# RoboSkinRev2.net
KiCad netlist of a schematic drawn in EAGLE
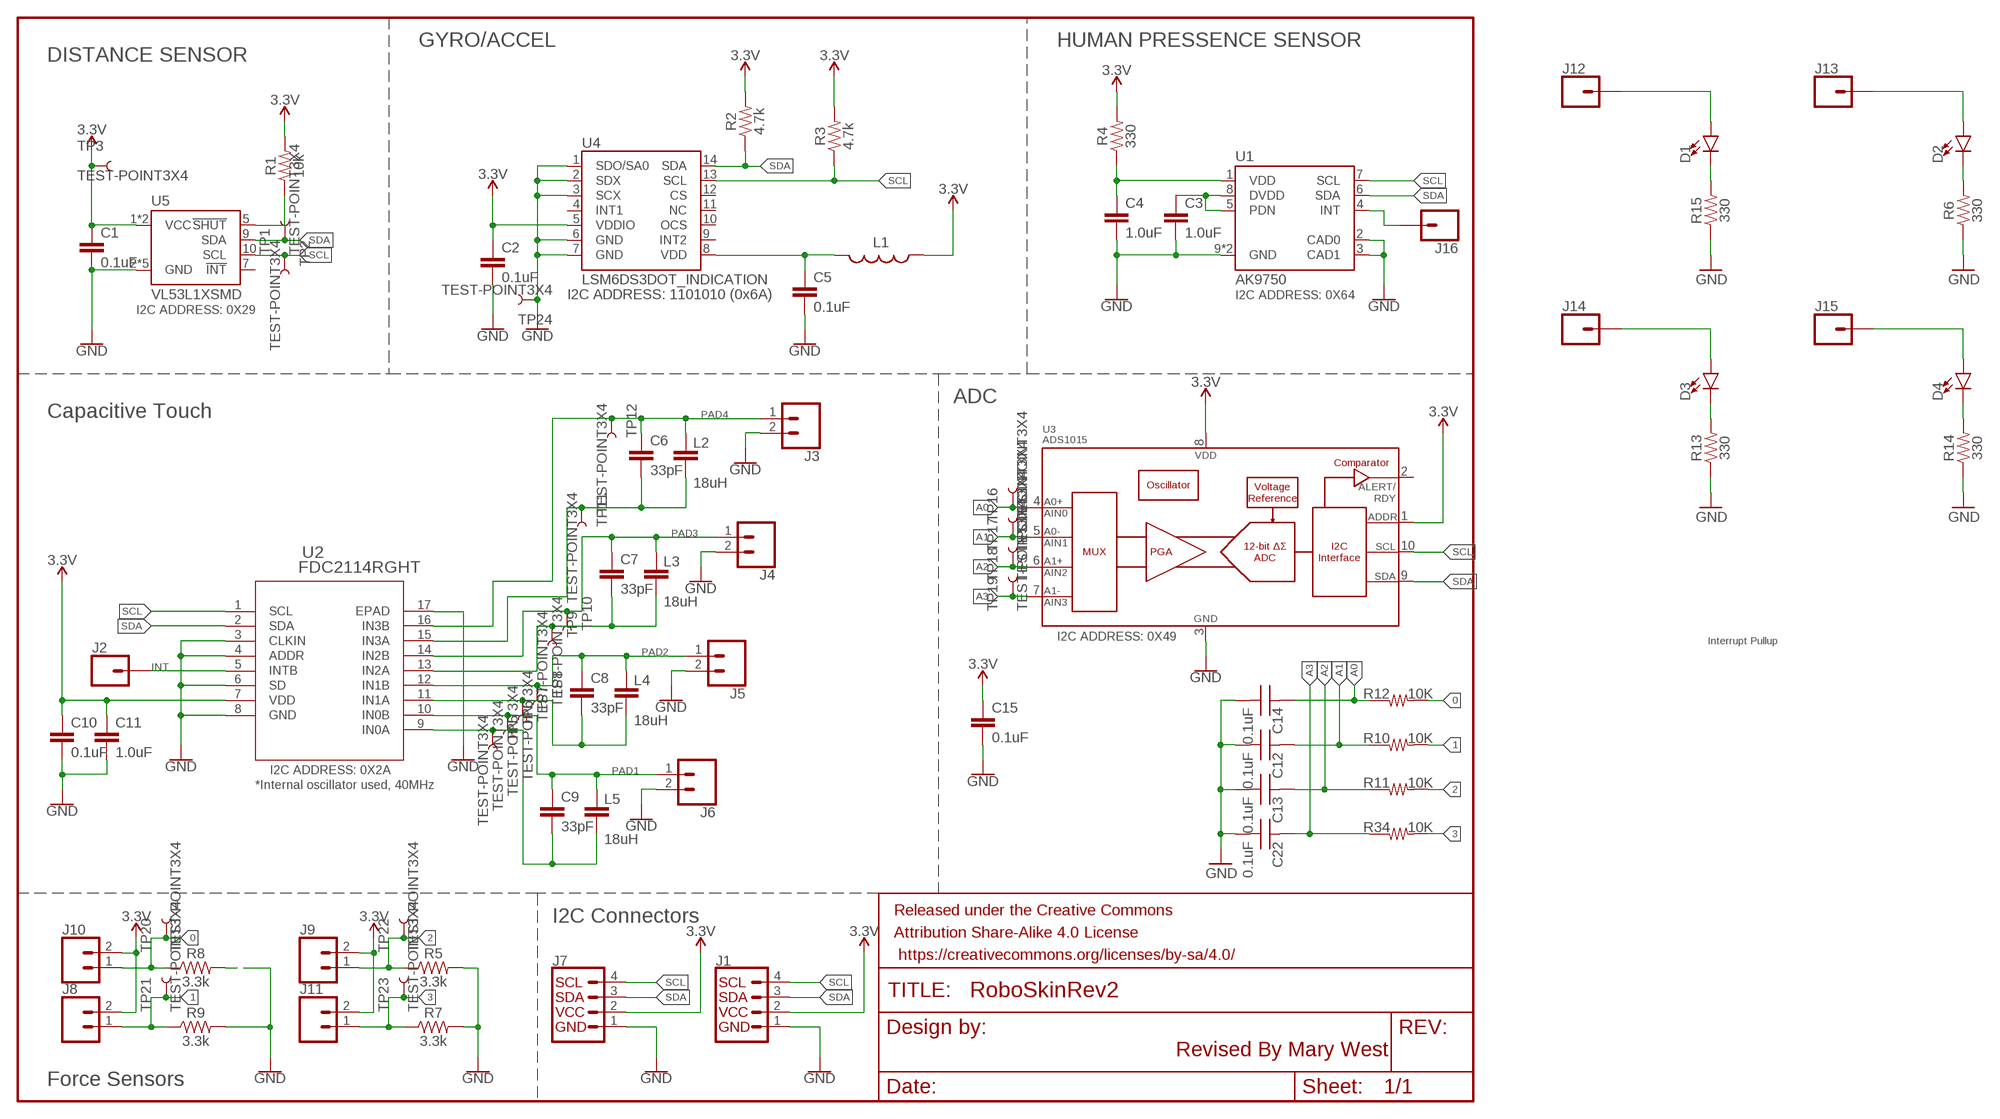
[diagram p0: schematic, sheet 1]

(export (version "E")
  (design (tool "Eeschema 10.0.6"))
  (components
    (comp (ref "C1")
      (value "0.1uF")
      (footprint "eagle-import:0603")
      (libsource (lib "eagle-import") (part "0.1UF-0603-25V-(+80/-20%)"))
    )
    (comp (ref "C2")
      (value "0.1uF")
      (footprint "eagle-import:0603")
      (libsource (lib "eagle-import") (part "0.1UF-0603-25V-(+80/-20%)"))
    )
    (comp (ref "C3")
      (value "1.0uF")
      (footprint "eagle-import:0603")
      (libsource (lib "eagle-import") (part "1.0UF-0603-16V-10%"))
    )
    (comp (ref "C4")
      (value "1.0uF")
      (footprint "eagle-import:0603")
      (libsource (lib "eagle-import") (part "1.0UF-0603-16V-10%"))
    )
    (comp (ref "C5")
      (value "0.1uF")
      (footprint "eagle-import:0603")
      (libsource (lib "eagle-import") (part "0.1UF-0603-25V-(+80/-20%)"))
    )
    (comp (ref "C6")
      (value "33pF")
      (footprint "eagle-import:0603")
      (libsource (lib "eagle-import") (part "33PF-0603-50V-5%"))
    )
    (comp (ref "C7")
      (value "33pF")
      (footprint "eagle-import:0603")
      (libsource (lib "eagle-import") (part "33PF-0603-50V-5%"))
    )
    (comp (ref "C8")
      (value "33pF")
      (footprint "eagle-import:0603")
      (libsource (lib "eagle-import") (part "33PF-0603-50V-5%"))
    )
    (comp (ref "C9")
      (value "33pF")
      (footprint "eagle-import:0603")
      (libsource (lib "eagle-import") (part "33PF-0603-50V-5%"))
    )
    (comp (ref "C10")
      (value "0.1uF")
      (footprint "eagle-import:0603")
      (libsource (lib "eagle-import") (part "0.1UF-0603-25V-(+80/-20%)"))
    )
    (comp (ref "C11")
      (value "1.0uF")
      (footprint "eagle-import:0603")
      (libsource (lib "eagle-import") (part "1.0UF-0603-16V-10%"))
    )
    (comp (ref "C12")
      (value "0.1uF")
      (footprint "eagle-import:0603_SILK")
      (fields (field (name "PARTNO") "GRM188R70J104KA01D"))
      (libsource (lib "eagle-import") (part "CAPACITORC_0603_SILK"))
    )
    (comp (ref "C13")
      (value "0.1uF")
      (footprint "eagle-import:0603_SILK")
      (fields (field (name "PARTNO") "GRM188R70J104KA01D"))
      (libsource (lib "eagle-import") (part "CAPACITORC_0603_SILK"))
    )
    (comp (ref "C14")
      (value "0.1uF")
      (footprint "eagle-import:0603_SILK")
      (fields (field (name "PARTNO") "GRM188R70J104KA01D"))
      (libsource (lib "eagle-import") (part "CAPACITORC_0603_SILK"))
    )
    (comp (ref "C15")
      (value "0.1uF")
      (footprint "eagle-import:0603")
      (libsource (lib "eagle-import") (part "0.1UF-0603-25V-(+80/-20%)"))
    )
    (comp (ref "C22")
      (value "0.1uF")
      (footprint "eagle-import:0603_SILK")
      (fields (field (name "PARTNO") "GRM188R70J104KA01D"))
      (libsource (lib "eagle-import") (part "CAPACITORC_0603_SILK"))
    )
    (comp (ref "D1")
      (value "LED1206")
      (footprint "eagle-import:LED-1206")
      (libsource (lib "eagle-import") (part "LED1206"))
    )
    (comp (ref "D2")
      (value "LED1206")
      (footprint "eagle-import:LED-1206")
      (libsource (lib "eagle-import") (part "LED1206"))
    )
    (comp (ref "D3")
      (value "LED1206")
      (footprint "eagle-import:LED-1206")
      (libsource (lib "eagle-import") (part "LED1206"))
    )
    (comp (ref "D4")
      (value "LED1206")
      (footprint "eagle-import:LED-1206")
      (libsource (lib "eagle-import") (part "LED1206"))
    )
    (comp (ref "FRAME1")
      (value "FRAME-LETTERNO_PACKAGE")
      (footprint "eagle-import:DUMMY")
      (fields (field (name "DESIGNER") "Nobody"))
      (libsource (lib "eagle-import") (part "FRAME-LETTERNO_PACKAGE"))
    )
    (comp (ref "J1")
      (value "QWIIC_CONNECTORJS-1MM")
      (footprint "eagle-import:1X04_1MM_RA")
      (libsource (lib "eagle-import") (part "QWIIC_CONNECTORJS-1MM"))
    )
    (comp (ref "J2")
      (value "CONN_01")
      (footprint "eagle-import:1X01")
      (libsource (lib "eagle-import") (part "CONN_01"))
    )
    (comp (ref "J3")
      (value "CONN_02")
      (footprint "eagle-import:1X02")
      (libsource (lib "eagle-import") (part "CONN_02"))
    )
    (comp (ref "J4")
      (value "CONN_02")
      (footprint "eagle-import:1X02")
      (libsource (lib "eagle-import") (part "CONN_02"))
    )
    (comp (ref "J5")
      (value "CONN_02")
      (footprint "eagle-import:1X02")
      (libsource (lib "eagle-import") (part "CONN_02"))
    )
    (comp (ref "J6")
      (value "CONN_02")
      (footprint "eagle-import:1X02")
      (libsource (lib "eagle-import") (part "CONN_02"))
    )
    (comp (ref "J7")
      (value "QWIIC_CONNECTORJS-1MM")
      (footprint "eagle-import:1X04_1MM_RA")
      (libsource (lib "eagle-import") (part "QWIIC_CONNECTORJS-1MM"))
    )
    (comp (ref "J8")
      (value "CONN_02")
      (footprint "eagle-import:1X02")
      (libsource (lib "eagle-import") (part "CONN_02"))
    )
    (comp (ref "J9")
      (value "CONN_02")
      (footprint "eagle-import:1X02")
      (libsource (lib "eagle-import") (part "CONN_02"))
    )
    (comp (ref "J10")
      (value "CONN_02")
      (footprint "eagle-import:1X02")
      (libsource (lib "eagle-import") (part "CONN_02"))
    )
    (comp (ref "J11")
      (value "CONN_02")
      (footprint "eagle-import:1X02")
      (libsource (lib "eagle-import") (part "CONN_02"))
    )
    (comp (ref "J12")
      (value "CONN_01")
      (footprint "eagle-import:1X01")
      (libsource (lib "eagle-import") (part "CONN_01"))
    )
    (comp (ref "J13")
      (value "CONN_01")
      (footprint "eagle-import:1X01")
      (libsource (lib "eagle-import") (part "CONN_01"))
    )
    (comp (ref "J14")
      (value "CONN_01")
      (footprint "eagle-import:1X01")
      (libsource (lib "eagle-import") (part "CONN_01"))
    )
    (comp (ref "J15")
      (value "CONN_01")
      (footprint "eagle-import:1X01")
      (libsource (lib "eagle-import") (part "CONN_01"))
    )
    (comp (ref "J16")
      (value "CONN_01PTH_NO_SILK_YES_STOP")
      (footprint "eagle-import:1X01_NO_SILK")
      (libsource (lib "eagle-import") (part "CONN_01PTH_NO_SILK_YES_STOP"))
    )
    (comp (ref "L1")
      (value "RES-07859")
      (footprint "eagle-import:0603")
      (libsource (lib "eagle-import") (part "INDUCTOR30OHM,1.8A"))
    )
    (comp (ref "L2")
      (value "18uH")
      (footprint "eagle-import:1210")
      (libsource (lib "eagle-import") (part "100UF6.3V20%(1210)"))
    )
    (comp (ref "L3")
      (value "18uH")
      (footprint "eagle-import:1210")
      (libsource (lib "eagle-import") (part "100UF6.3V20%(1210)"))
    )
    (comp (ref "L4")
      (value "18uH")
      (footprint "eagle-import:1210")
      (libsource (lib "eagle-import") (part "100UF6.3V20%(1210)"))
    )
    (comp (ref "L5")
      (value "18uH")
      (footprint "eagle-import:1210")
      (libsource (lib "eagle-import") (part "100UF6.3V20%(1210)"))
    )
    (comp (ref "R1")
      (value "10k")
      (footprint "eagle-import:0603")
      (libsource (lib "eagle-import") (part "10KOHM-0603-1/10W-1%"))
    )
    (comp (ref "R2")
      (value "4.7k")
      (footprint "eagle-import:0603")
      (libsource (lib "eagle-import") (part "4.7KOHM-0603-1/10W-1%"))
    )
    (comp (ref "R3")
      (value "4.7k")
      (footprint "eagle-import:0603")
      (libsource (lib "eagle-import") (part "4.7KOHM-0603-1/10W-1%"))
    )
    (comp (ref "R4")
      (value "330")
      (footprint "eagle-import:0603")
      (libsource (lib "eagle-import") (part "SparkFun-Resistors_532_330OHM-0603-1/10W-1%"))
    )
    (comp (ref "R5")
      (value "3.3k")
      (footprint "eagle-import:0603")
      (libsource (lib "eagle-import") (part "3.3KOHM-0603-1/10W-1%"))
    )
    (comp (ref "R6")
      (value "330")
      (footprint "eagle-import:0603")
      (libsource (lib "eagle-import") (part "330OHM-0603-1/10W-1%"))
    )
    (comp (ref "R7")
      (value "3.3k")
      (footprint "eagle-import:0603")
      (libsource (lib "eagle-import") (part "3.3KOHM-0603-1/10W-1%"))
    )
    (comp (ref "R8")
      (value "3.3k")
      (footprint "eagle-import:0603")
      (libsource (lib "eagle-import") (part "3.3KOHM-0603-1/10W-1%"))
    )
    (comp (ref "R9")
      (value "3.3k")
      (footprint "eagle-import:0603")
      (libsource (lib "eagle-import") (part "3.3KOHM-0603-1/10W-1%"))
    )
    (comp (ref "R10")
      (value "10K")
      (footprint "eagle-import:0603_SILK")
      (fields (field (name "PARTNO") "CR0603-FX-1002ELF"))
      (libsource (lib "eagle-import") (part "RESISTORR_0603_SILK"))
    )
    (comp (ref "R11")
      (value "10K")
      (footprint "eagle-import:0603_SILK")
      (fields (field (name "PARTNO") "CR0603-FX-1002ELF"))
      (libsource (lib "eagle-import") (part "RESISTORR_0603_SILK"))
    )
    (comp (ref "R12")
      (value "10K")
      (footprint "eagle-import:0603_SILK")
      (fields (field (name "PARTNO") "CR0603-FX-1002ELF"))
      (libsource (lib "eagle-import") (part "RESISTORR_0603_SILK"))
    )
    (comp (ref "R13")
      (value "330")
      (footprint "eagle-import:0603")
      (libsource (lib "eagle-import") (part "330OHM-0603-1/10W-1%"))
    )
    (comp (ref "R14")
      (value "330")
      (footprint "eagle-import:0603")
      (libsource (lib "eagle-import") (part "330OHM-0603-1/10W-1%"))
    )
    (comp (ref "R15")
      (value "330")
      (footprint "eagle-import:0603")
      (libsource (lib "eagle-import") (part "330OHM-0603-1/10W-1%"))
    )
    (comp (ref "R34")
      (value "10K")
      (footprint "eagle-import:0603_SILK")
      (fields (field (name "PARTNO") "CR0603-FX-1002ELF"))
      (libsource (lib "eagle-import") (part "RESISTORR_0603_SILK"))
    )
    (comp (ref "TP1")
      (value "TEST-POINT3X4")
      (footprint "eagle-import:PAD.03X.04")
      (libsource (lib "eagle-import") (part "TEST-POINT3X4"))
    )
    (comp (ref "TP2")
      (value "TEST-POINT3X4")
      (footprint "eagle-import:PAD.03X.04")
      (libsource (lib "eagle-import") (part "TEST-POINT3X4"))
    )
    (comp (ref "TP3")
      (value "TEST-POINT3X4")
      (footprint "eagle-import:PAD.03X.04")
      (libsource (lib "eagle-import") (part "TEST-POINT3X4"))
    )
    (comp (ref "TP5")
      (value "TEST-POINT3X4")
      (footprint "eagle-import:PAD.03X.04")
      (libsource (lib "eagle-import") (part "TEST-POINT3X4"))
    )
    (comp (ref "TP6")
      (value "TEST-POINT3X4")
      (footprint "eagle-import:PAD.03X.04")
      (libsource (lib "eagle-import") (part "TEST-POINT3X4"))
    )
    (comp (ref "TP7")
      (value "TEST-POINT3X4")
      (footprint "eagle-import:PAD.03X.04")
      (libsource (lib "eagle-import") (part "TEST-POINT3X4"))
    )
    (comp (ref "TP8")
      (value "TEST-POINT3X4")
      (footprint "eagle-import:PAD.03X.04")
      (libsource (lib "eagle-import") (part "TEST-POINT3X4"))
    )
    (comp (ref "TP9")
      (value "TEST-POINT3X4")
      (footprint "eagle-import:PAD.03X.04")
      (libsource (lib "eagle-import") (part "TEST-POINT3X4"))
    )
    (comp (ref "TP10")
      (value "TEST-POINT3X4")
      (footprint "eagle-import:PAD.03X.04")
      (libsource (lib "eagle-import") (part "TEST-POINT3X4"))
    )
    (comp (ref "TP11")
      (value "TEST-POINT3X4")
      (footprint "eagle-import:PAD.03X.04")
      (libsource (lib "eagle-import") (part "TEST-POINT3X4"))
    )
    (comp (ref "TP12")
      (value "TEST-POINT3X4")
      (footprint "eagle-import:PAD.03X.04")
      (libsource (lib "eagle-import") (part "TEST-POINT3X4"))
    )
    (comp (ref "TP16")
      (value "TEST-POINT3X4")
      (footprint "eagle-import:PAD.03X.04")
      (libsource (lib "eagle-import") (part "TEST-POINT3X4"))
    )
    (comp (ref "TP17")
      (value "TEST-POINT3X4")
      (footprint "eagle-import:PAD.03X.04")
      (libsource (lib "eagle-import") (part "TEST-POINT3X4"))
    )
    (comp (ref "TP18")
      (value "TEST-POINT3X4")
      (footprint "eagle-import:PAD.03X.04")
      (libsource (lib "eagle-import") (part "TEST-POINT3X4"))
    )
    (comp (ref "TP19")
      (value "TEST-POINT3X4")
      (footprint "eagle-import:PAD.03X.04")
      (libsource (lib "eagle-import") (part "TEST-POINT3X4"))
    )
    (comp (ref "TP20")
      (value "TEST-POINT3X4")
      (footprint "eagle-import:PAD.03X.04")
      (libsource (lib "eagle-import") (part "TEST-POINT3X4"))
    )
    (comp (ref "TP21")
      (value "TEST-POINT3X4")
      (footprint "eagle-import:PAD.03X.04")
      (libsource (lib "eagle-import") (part "TEST-POINT3X4"))
    )
    (comp (ref "TP22")
      (value "TEST-POINT3X4")
      (footprint "eagle-import:PAD.03X.04")
      (libsource (lib "eagle-import") (part "TEST-POINT3X4"))
    )
    (comp (ref "TP23")
      (value "TEST-POINT3X4")
      (footprint "eagle-import:PAD.03X.04")
      (libsource (lib "eagle-import") (part "TEST-POINT3X4"))
    )
    (comp (ref "TP24")
      (value "TEST-POINT3X4")
      (footprint "eagle-import:PAD.03X.04")
      (libsource (lib "eagle-import") (part "TEST-POINT3X4"))
    )
    (comp (ref "U1")
      (value "AK9750")
      (footprint "eagle-import:SON10")
      (libsource (lib "eagle-import") (part "AK9750"))
    )
    (comp (ref "U2")
      (value "FDC2114RGHT")
      (footprint "eagle-import:RGH16")
      (fields (field (name "COPYRIGHT") "Copyright (C) 2018 Accelerated Designs. All rights reserved"))
      (libsource (lib "eagle-import") (part "FDC2114RGHT"))
    )
    (comp (ref "U3")
      (value "ADS1015")
      (footprint "eagle-import:MSOP10")
      (libsource (lib "eagle-import") (part "ADS1015"))
    )
    (comp (ref "U4")
      (value "LSM6DS3DOT_INDICATION")
      (footprint "eagle-import:LGA14L_DOT_INDICATOR")
      (libsource (lib "eagle-import") (part "LSM6DS3DOT_INDICATION"))
    )
    (comp (ref "U5")
      (value "VL53L1XSMD")
      (footprint "eagle-import:VL53L1X")
      (libsource (lib "eagle-import") (part "VL53L1XSMD"))
    )
  )
  (nets
    (net (code "1") (name "/INT") (class "Default")
      (node (ref "J2") (pin "1") (pinfunction "1_1") (pintype "passive"))
      (node (ref "U2") (pin "5") (pinfunction "INTB_5") (pintype "output"))
    )
    (net (code "2") (name "/PAD1") (class "Default")
      (node (ref "C9") (pin "1") (pinfunction "1_1") (pintype "passive"))
      (node (ref "J6") (pin "1") (pinfunction "1_1") (pintype "passive"))
      (node (ref "L5") (pin "1") (pinfunction "1_1") (pintype "passive"))
      (node (ref "TP6") (pin "P$1") (pinfunction "1_P$1") (pintype "bidirectional"))
      (node (ref "U2") (pin "10") (pinfunction "IN0B_10") (pintype "input"))
    )
    (net (code "3") (name "/PAD2") (class "Default")
      (node (ref "C8") (pin "1") (pinfunction "1_1") (pintype "passive"))
      (node (ref "J5") (pin "1") (pinfunction "1_1") (pintype "passive"))
      (node (ref "L4") (pin "1") (pinfunction "1_1") (pintype "passive"))
      (node (ref "TP8") (pin "P$1") (pinfunction "1_P$1") (pintype "bidirectional"))
      (node (ref "U2") (pin "12") (pinfunction "IN1B_12") (pintype "input"))
    )
    (net (code "4") (name "/PAD3") (class "Default")
      (node (ref "C7") (pin "1") (pinfunction "1_1") (pintype "passive"))
      (node (ref "J4") (pin "1") (pinfunction "1_1") (pintype "passive"))
      (node (ref "L3") (pin "1") (pinfunction "1_1") (pintype "passive"))
      (node (ref "TP10") (pin "P$1") (pinfunction "1_P$1") (pintype "bidirectional"))
      (node (ref "U2") (pin "14") (pinfunction "IN2B_14") (pintype "input"))
    )
    (net (code "5") (name "/PAD4") (class "Default")
      (node (ref "C6") (pin "1") (pinfunction "1_1") (pintype "passive"))
      (node (ref "J3") (pin "1") (pinfunction "1_1") (pintype "passive"))
      (node (ref "L2") (pin "1") (pinfunction "1_1") (pintype "passive"))
      (node (ref "TP12") (pin "P$1") (pinfunction "1_P$1") (pintype "bidirectional"))
      (node (ref "U2") (pin "16") (pinfunction "IN3B_16") (pintype "input"))
    )
    (net (code "6") (name "0") (class "Default")
      (node (ref "J10") (pin "1") (pinfunction "1_1") (pintype "passive"))
      (node (ref "R12") (pin "P2") (pinfunction "2_P2") (pintype "passive"))
      (node (ref "R8") (pin "1") (pinfunction "1_1") (pintype "passive"))
      (node (ref "TP20") (pin "P$1") (pinfunction "1_P$1") (pintype "bidirectional"))
    )
    (net (code "7") (name "1") (class "Default")
      (node (ref "J8") (pin "1") (pinfunction "1_1") (pintype "passive"))
      (node (ref "R10") (pin "P2") (pinfunction "2_P2") (pintype "passive"))
      (node (ref "R9") (pin "1") (pinfunction "1_1") (pintype "passive"))
      (node (ref "TP21") (pin "P$1") (pinfunction "1_P$1") (pintype "bidirectional"))
    )
    (net (code "8") (name "2") (class "Default")
      (node (ref "J9") (pin "1") (pinfunction "1_1") (pintype "passive"))
      (node (ref "R11") (pin "P2") (pinfunction "2_P2") (pintype "passive"))
      (node (ref "R5") (pin "1") (pinfunction "1_1") (pintype "passive"))
      (node (ref "TP22") (pin "P$1") (pinfunction "1_P$1") (pintype "bidirectional"))
    )
    (net (code "9") (name "3") (class "Default")
      (node (ref "J11") (pin "1") (pinfunction "1_1") (pintype "passive"))
      (node (ref "R34") (pin "P2") (pinfunction "2_P2") (pintype "passive"))
      (node (ref "R7") (pin "1") (pinfunction "1_1") (pintype "passive"))
      (node (ref "TP23") (pin "P$1") (pinfunction "1_P$1") (pintype "bidirectional"))
    )
    (net (code "10") (name "3.3V") (class "Default")
      (node (ref "C1") (pin "1") (pinfunction "1_1") (pintype "passive"))
      (node (ref "C10") (pin "1") (pinfunction "1_1") (pintype "passive"))
      (node (ref "C11") (pin "1") (pinfunction "1_1") (pintype "passive"))
      (node (ref "C15") (pin "1") (pinfunction "1_1") (pintype "passive"))
      (node (ref "C2") (pin "1") (pinfunction "1_1") (pintype "passive"))
      (node (ref "J1") (pin "2") (pinfunction "VCC_2") (pintype "power_in"))
      (node (ref "J10") (pin "2") (pinfunction "2_2") (pintype "passive"))
      (node (ref "J11") (pin "2") (pinfunction "2_2") (pintype "passive"))
      (node (ref "J7") (pin "2") (pinfunction "VCC_2") (pintype "power_in"))
      (node (ref "J8") (pin "2") (pinfunction "2_2") (pintype "passive"))
      (node (ref "J9") (pin "2") (pinfunction "2_2") (pintype "passive"))
      (node (ref "L1") (pin "1") (pinfunction "1_1") (pintype "passive"))
      (node (ref "R1") (pin "2") (pinfunction "2_2") (pintype "passive"))
      (node (ref "R2") (pin "2") (pinfunction "2_2") (pintype "passive"))
      (node (ref "R3") (pin "2") (pinfunction "2_2") (pintype "passive"))
      (node (ref "R4") (pin "2") (pinfunction "2_2") (pintype "passive"))
      (node (ref "TP3") (pin "P$1") (pinfunction "1_P$1") (pintype "bidirectional"))
      (node (ref "U2") (pin "7") (pinfunction "VDD_7") (pintype "power_in"))
      (node (ref "U3") (pin "1") (pinfunction "ADDR_1") (pintype "bidirectional"))
      (node (ref "U3") (pin "8") (pinfunction "VDD_8") (pintype "bidirectional"))
      (node (ref "U4") (pin "5") (pinfunction "VDDIO_5") (pintype "bidirectional"))
      (node (ref "U5") (pin "1") (pinfunction "VCC_1") (pintype "bidirectional"))
      (node (ref "U5") (pin "11") (pinfunction "VCC_11") (pintype "bidirectional"))
    )
    (net (code "11") (name "A0") (class "Default")
      (node (ref "C14") (pin "P1") (pinfunction "1_P1") (pintype "passive"))
      (node (ref "R12") (pin "P1") (pinfunction "1_P1") (pintype "passive"))
      (node (ref "TP16") (pin "P$1") (pinfunction "1_P$1") (pintype "bidirectional"))
      (node (ref "U3") (pin "4") (pinfunction "AIN0_4") (pintype "bidirectional"))
    )
    (net (code "12") (name "A1") (class "Default")
      (node (ref "C12") (pin "P1") (pinfunction "1_P1") (pintype "passive"))
      (node (ref "R10") (pin "P1") (pinfunction "1_P1") (pintype "passive"))
      (node (ref "TP17") (pin "P$1") (pinfunction "1_P$1") (pintype "bidirectional"))
      (node (ref "U3") (pin "5") (pinfunction "AIN1_5") (pintype "bidirectional"))
    )
    (net (code "13") (name "A2") (class "Default")
      (node (ref "C13") (pin "P1") (pinfunction "1_P1") (pintype "passive"))
      (node (ref "R11") (pin "P1") (pinfunction "1_P1") (pintype "passive"))
      (node (ref "TP18") (pin "P$1") (pinfunction "1_P$1") (pintype "bidirectional"))
      (node (ref "U3") (pin "6") (pinfunction "AIN2_6") (pintype "bidirectional"))
    )
    (net (code "14") (name "A3") (class "Default")
      (node (ref "C22") (pin "P1") (pinfunction "1_P1") (pintype "passive"))
      (node (ref "R34") (pin "P1") (pinfunction "1_P1") (pintype "passive"))
      (node (ref "TP19") (pin "P$1") (pinfunction "1_P$1") (pintype "bidirectional"))
      (node (ref "U3") (pin "7") (pinfunction "AIN3_7") (pintype "bidirectional"))
    )
    (net (code "15") (name "GND") (class "Default")
      (node (ref "C1") (pin "2") (pinfunction "2_2") (pintype "passive"))
      (node (ref "C10") (pin "2") (pinfunction "2_2") (pintype "passive"))
      (node (ref "C11") (pin "2") (pinfunction "2_2") (pintype "passive"))
      (node (ref "C12") (pin "P2") (pinfunction "2_P2") (pintype "passive"))
      (node (ref "C13") (pin "P2") (pinfunction "2_P2") (pintype "passive"))
      (node (ref "C14") (pin "P2") (pinfunction "2_P2") (pintype "passive"))
      (node (ref "C15") (pin "2") (pinfunction "2_2") (pintype "passive"))
      (node (ref "C2") (pin "2") (pinfunction "2_2") (pintype "passive"))
      (node (ref "C22") (pin "P2") (pinfunction "2_P2") (pintype "passive"))
      (node (ref "C3") (pin "2") (pinfunction "2_2") (pintype "passive"))
      (node (ref "C4") (pin "2") (pinfunction "2_2") (pintype "passive"))
      (node (ref "C5") (pin "2") (pinfunction "2_2") (pintype "passive"))
      (node (ref "J1") (pin "1") (pinfunction "GND_1") (pintype "power_in"))
      (node (ref "J3") (pin "2") (pinfunction "2_2") (pintype "passive"))
      (node (ref "J4") (pin "2") (pinfunction "2_2") (pintype "passive"))
      (node (ref "J5") (pin "2") (pinfunction "2_2") (pintype "passive"))
      (node (ref "J6") (pin "2") (pinfunction "2_2") (pintype "passive"))
      (node (ref "J7") (pin "1") (pinfunction "GND_1") (pintype "power_in"))
      (node (ref "R13") (pin "1") (pinfunction "1_1") (pintype "passive"))
      (node (ref "R14") (pin "1") (pinfunction "1_1") (pintype "passive"))
      (node (ref "R15") (pin "1") (pinfunction "1_1") (pintype "passive"))
      (node (ref "R5") (pin "2") (pinfunction "2_2") (pintype "passive"))
      (node (ref "R6") (pin "1") (pinfunction "1_1") (pintype "passive"))
      (node (ref "R7") (pin "2") (pinfunction "2_2") (pintype "passive"))
      (node (ref "R8") (pin "2") (pinfunction "2_2") (pintype "passive"))
      (node (ref "R9") (pin "2") (pinfunction "2_2") (pintype "passive"))
      (node (ref "TP24") (pin "P$1") (pinfunction "1_P$1") (pintype "bidirectional"))
      (node (ref "U1") (pin "10") (pinfunction "GND_10") (pintype "bidirectional"))
      (node (ref "U1") (pin "2") (pinfunction "CAD0_2") (pintype "bidirectional"))
      (node (ref "U1") (pin "3") (pinfunction "CAD1_3") (pintype "bidirectional"))
      (node (ref "U1") (pin "9") (pinfunction "GND_9") (pintype "bidirectional"))
      (node (ref "U2") (pin "17") (pinfunction "EPAD_17") (pintype "passive"))
      (node (ref "U2") (pin "3") (pinfunction "CLKIN_3") (pintype "input"))
      (node (ref "U2") (pin "4") (pinfunction "ADDR_4") (pintype "input"))
      (node (ref "U2") (pin "6") (pinfunction "SD_6") (pintype "input"))
      (node (ref "U2") (pin "8") (pinfunction "GND_8") (pintype "power_in"))
      (node (ref "U3") (pin "3") (pinfunction "VSS_3") (pintype "bidirectional"))
      (node (ref "U4") (pin "1") (pinfunction "SDO/SA0_1") (pintype "bidirectional"))
      (node (ref "U4") (pin "2") (pinfunction "SDX_2") (pintype "bidirectional"))
      (node (ref "U4") (pin "3") (pinfunction "SCX_3") (pintype "bidirectional"))
      (node (ref "U4") (pin "6") (pinfunction "GND_6") (pintype "bidirectional"))
      (node (ref "U4") (pin "7") (pinfunction "GND_7") (pintype "bidirectional"))
      (node (ref "U5") (pin "12") (pinfunction "GND_12") (pintype "bidirectional"))
      (node (ref "U5") (pin "2") (pinfunction "GND_2") (pintype "bidirectional"))
      (node (ref "U5") (pin "3") (pinfunction "GND_3") (pintype "bidirectional"))
      (node (ref "U5") (pin "4") (pinfunction "GND_4") (pintype "bidirectional"))
      (node (ref "U5") (pin "6") (pinfunction "GND_6") (pintype "bidirectional"))
    )
    (net (code "16") (name "Net-(D1-PadA)") (class "Default")
      (node (ref "D1") (pin "A") (pinfunction "A_A") (pintype "passive"))
      (node (ref "J12") (pin "1") (pinfunction "1_1") (pintype "passive"))
    )
    (net (code "17") (name "Net-(D1-PadC)") (class "Default")
      (node (ref "D1") (pin "C") (pinfunction "C_C") (pintype "passive"))
      (node (ref "R15") (pin "2") (pinfunction "2_2") (pintype "passive"))
    )
    (net (code "18") (name "Net-(D2-PadA)") (class "Default")
      (node (ref "D2") (pin "A") (pinfunction "A_A") (pintype "passive"))
      (node (ref "J13") (pin "1") (pinfunction "1_1") (pintype "passive"))
    )
    (net (code "19") (name "Net-(D2-PadC)") (class "Default")
      (node (ref "D2") (pin "C") (pinfunction "C_C") (pintype "passive"))
      (node (ref "R6") (pin "2") (pinfunction "2_2") (pintype "passive"))
    )
    (net (code "20") (name "Net-(D3-PadA)") (class "Default")
      (node (ref "D3") (pin "A") (pinfunction "A_A") (pintype "passive"))
      (node (ref "J14") (pin "1") (pinfunction "1_1") (pintype "passive"))
    )
    (net (code "21") (name "Net-(D3-PadC)") (class "Default")
      (node (ref "D3") (pin "C") (pinfunction "C_C") (pintype "passive"))
      (node (ref "R13") (pin "2") (pinfunction "2_2") (pintype "passive"))
    )
    (net (code "22") (name "Net-(D4-PadA)") (class "Default")
      (node (ref "D4") (pin "A") (pinfunction "A_A") (pintype "passive"))
      (node (ref "J15") (pin "1") (pinfunction "1_1") (pintype "passive"))
    )
    (net (code "23") (name "Net-(D4-PadC)") (class "Default")
      (node (ref "D4") (pin "C") (pinfunction "C_C") (pintype "passive"))
      (node (ref "R14") (pin "2") (pinfunction "2_2") (pintype "passive"))
    )
    (net (code "24") (name "Net-(TP5-1)") (class "Default")
      (node (ref "C9") (pin "2") (pinfunction "2_2") (pintype "passive"))
      (node (ref "L5") (pin "2") (pinfunction "2_2") (pintype "passive"))
      (node (ref "TP5") (pin "P$1") (pinfunction "1_P$1") (pintype "bidirectional"))
      (node (ref "U2") (pin "9") (pinfunction "IN0A_9") (pintype "input"))
    )
    (net (code "25") (name "Net-(TP7-1)") (class "Default")
      (node (ref "C8") (pin "2") (pinfunction "2_2") (pintype "passive"))
      (node (ref "L4") (pin "2") (pinfunction "2_2") (pintype "passive"))
      (node (ref "TP7") (pin "P$1") (pinfunction "1_P$1") (pintype "bidirectional"))
      (node (ref "U2") (pin "11") (pinfunction "IN1A_11") (pintype "input"))
    )
    (net (code "26") (name "Net-(TP9-1)") (class "Default")
      (node (ref "C7") (pin "2") (pinfunction "2_2") (pintype "passive"))
      (node (ref "L3") (pin "2") (pinfunction "2_2") (pintype "passive"))
      (node (ref "TP9") (pin "P$1") (pinfunction "1_P$1") (pintype "bidirectional"))
      (node (ref "U2") (pin "13") (pinfunction "IN2A_13") (pintype "input"))
    )
    (net (code "27") (name "Net-(TP11-1)") (class "Default")
      (node (ref "C6") (pin "2") (pinfunction "2_2") (pintype "passive"))
      (node (ref "L2") (pin "2") (pinfunction "2_2") (pintype "passive"))
      (node (ref "TP11") (pin "P$1") (pinfunction "1_P$1") (pintype "bidirectional"))
      (node (ref "U2") (pin "15") (pinfunction "IN3A_15") (pintype "input"))
    )
    (net (code "28") (name "Net-(U1-DVDD)") (class "Default")
      (node (ref "C3") (pin "1") (pinfunction "1_1") (pintype "passive"))
      (node (ref "U1") (pin "5") (pinfunction "PDN_5") (pintype "bidirectional"))
      (node (ref "U1") (pin "8") (pinfunction "DVDD_8") (pintype "bidirectional"))
    )
    (net (code "29") (name "Net-(U1-INT)") (class "Default")
      (node (ref "J16") (pin "1") (pinfunction "1_1") (pintype "passive"))
      (node (ref "U1") (pin "4") (pinfunction "INT_4") (pintype "bidirectional"))
    )
    (net (code "30") (name "Net-(U1-VDD)") (class "Default")
      (node (ref "C4") (pin "1") (pinfunction "1_1") (pintype "passive"))
      (node (ref "R4") (pin "1") (pinfunction "1_1") (pintype "passive"))
      (node (ref "U1") (pin "1") (pinfunction "VDD_1") (pintype "bidirectional"))
    )
    (net (code "31") (name "Net-(U4-VDD)") (class "Default")
      (node (ref "C5") (pin "1") (pinfunction "1_1") (pintype "passive"))
      (node (ref "L1") (pin "2") (pinfunction "2_2") (pintype "passive"))
      (node (ref "U4") (pin "8") (pinfunction "VDD_8") (pintype "bidirectional"))
    )
    (net (code "32") (name "Net-(U5-~{SHUT})") (class "Default")
      (node (ref "R1") (pin "1") (pinfunction "1_1") (pintype "passive"))
      (node (ref "U5") (pin "5") (pinfunction "~{SHUT}_5") (pintype "bidirectional"))
    )
    (net (code "33") (name "SCL") (class "Default")
      (node (ref "J1") (pin "4") (pinfunction "SCL_4") (pintype "passive"))
      (node (ref "J7") (pin "4") (pinfunction "SCL_4") (pintype "passive"))
      (node (ref "R3") (pin "1") (pinfunction "1_1") (pintype "passive"))
      (node (ref "TP2") (pin "P$1") (pinfunction "1_P$1") (pintype "bidirectional"))
      (node (ref "U1") (pin "7") (pinfunction "SCL_7") (pintype "bidirectional"))
      (node (ref "U2") (pin "1") (pinfunction "SCL_1") (pintype "input"))
      (node (ref "U3") (pin "10") (pinfunction "SCL_10") (pintype "bidirectional"))
      (node (ref "U4") (pin "13") (pinfunction "SCL_13") (pintype "bidirectional"))
      (node (ref "U5") (pin "10") (pinfunction "SCL_10") (pintype "bidirectional"))
    )
    (net (code "34") (name "SDA") (class "Default")
      (node (ref "J1") (pin "3") (pinfunction "SDA_3") (pintype "passive"))
      (node (ref "J7") (pin "3") (pinfunction "SDA_3") (pintype "passive"))
      (node (ref "R2") (pin "1") (pinfunction "1_1") (pintype "passive"))
      (node (ref "TP1") (pin "P$1") (pinfunction "1_P$1") (pintype "bidirectional"))
      (node (ref "U1") (pin "6") (pinfunction "SDA_6") (pintype "bidirectional"))
      (node (ref "U2") (pin "2") (pinfunction "SDA_2") (pintype "bidirectional"))
      (node (ref "U3") (pin "9") (pinfunction "SDA_9") (pintype "bidirectional"))
      (node (ref "U4") (pin "14") (pinfunction "SDA_14") (pintype "bidirectional"))
      (node (ref "U5") (pin "9") (pinfunction "SDA_9") (pintype "bidirectional"))
    )
    (net (code "35") (name "unconnected-(U3-ALERT{slash}RDY-Pad2)") (class "Default")
      (node (ref "U3") (pin "2") (pinfunction "ALERT/RDY_2") (pintype "bidirectional"))
    )
    (net (code "36") (name "unconnected-(U4-CS-Pad12)") (class "Default")
      (node (ref "U4") (pin "12") (pinfunction "CS_12") (pintype "bidirectional"))
    )
    (net (code "37") (name "unconnected-(U4-INT1-Pad4)") (class "Default")
      (node (ref "U4") (pin "4") (pinfunction "INT1_4") (pintype "bidirectional"))
    )
    (net (code "38") (name "unconnected-(U4-INT2-Pad9)") (class "Default")
      (node (ref "U4") (pin "9") (pinfunction "INT2_9") (pintype "bidirectional"))
    )
    (net (code "39") (name "unconnected-(U4-NC-Pad11)") (class "Default")
      (node (ref "U4") (pin "11") (pinfunction "NC_11") (pintype "bidirectional"))
    )
    (net (code "40") (name "unconnected-(U4-OCS-Pad10)") (class "Default")
      (node (ref "U4") (pin "10") (pinfunction "OCS_10") (pintype "bidirectional"))
    )
    (net (code "41") (name "unconnected-(U5-~{INT}-Pad7)") (class "Default")
      (node (ref "U5") (pin "7") (pinfunction "~{INT}_7") (pintype "bidirectional"))
    )
  )
)
